# power.net
KiCad netlist of a schematic drawn in Altium Designer
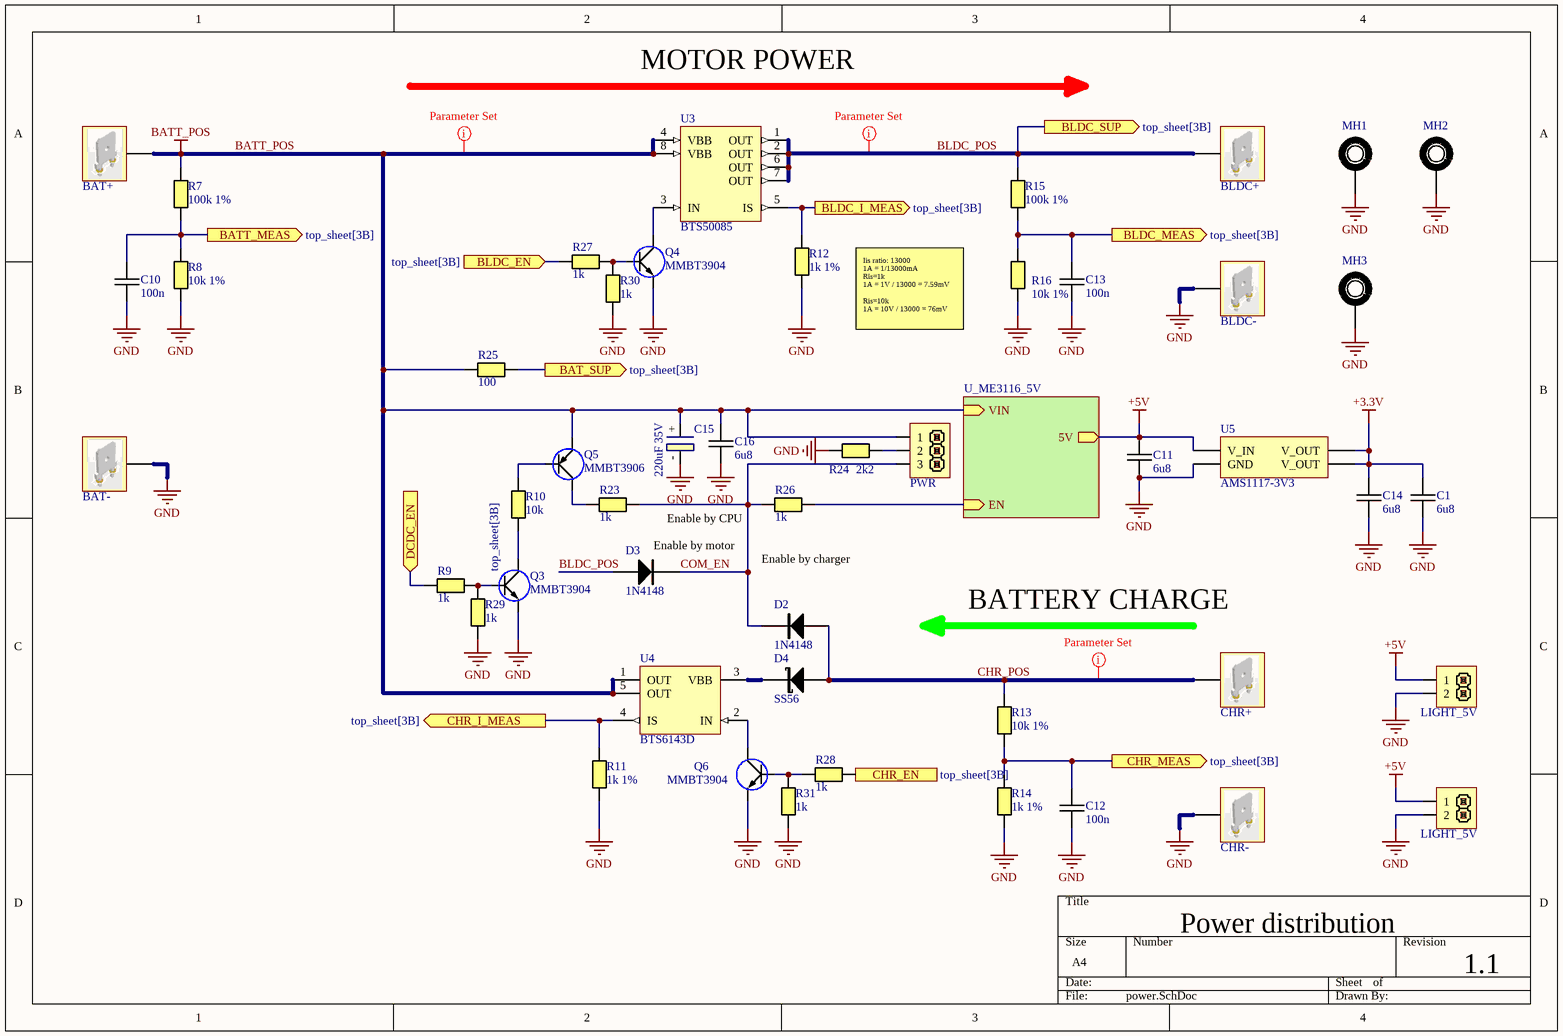
[diagram p0: power.SchDoc]

(export (version "E")
  (design (tool "Eeschema 10.0.6"))
  (components
    (comp (ref "BAT+")
      (value "Crimp 6.3 single PCB")
      (footprint "Crimp 6.3mm single PCB")
      (description "Straight Mount Angle PCB Tab Terminal")
      (libsource (lib "") (part "Crimp 6.3 single PCB_1"))
    )
    (comp (ref "BAT-")
      (value "Crimp 6.3 single PCB")
      (footprint "Crimp 6.3mm single PCB")
      (description "Straight Mount Angle PCB Tab Terminal")
      (libsource (lib "") (part "Crimp 6.3 single PCB_1"))
    )
    (comp (ref "BLDC+")
      (value "Crimp 6.3 single PCB")
      (footprint "Crimp 6.3mm single PCB")
      (description "Straight Mount Angle PCB Tab Terminal")
      (libsource (lib "Connectors") (part "Crimp 6.3 single PCB"))
    )
    (comp (ref "BLDC-")
      (value "Crimp 6.3 single PCB")
      (footprint "Crimp 6.3mm single PCB")
      (description "Straight Mount Angle PCB Tab Terminal")
      (libsource (lib "Connectors") (part "Crimp 6.3 single PCB"))
    )
    (comp (ref "C1")
      (value "6u8")
      (footprint "CAPC0805(2012)75_N")
      (description "Ceramic capacitor Medium density")
      (libsource (lib "Discrete") (part "Capacitor M"))
    )
    (comp (ref "C10")
      (value "100n")
      (footprint "CAPC0603(1608)55_N")
      (description "Ceramic capacitor Medium density")
      (libsource (lib "Discrete") (part "Capacitor M"))
    )
    (comp (ref "C11")
      (value "6u8")
      (footprint "CAPC0805(2012)75_N")
      (description "Ceramic capacitor Medium density")
      (libsource (lib "Discrete") (part "Capacitor M"))
    )
    (comp (ref "C12")
      (value "100n")
      (footprint "CAPC0603(1608)55_N")
      (description "Ceramic capacitor Medium density")
      (libsource (lib "Discrete") (part "Capacitor M"))
    )
    (comp (ref "C13")
      (value "100n")
      (footprint "CAPC0603(1608)55_N")
      (description "Ceramic capacitor Medium density")
      (libsource (lib "Discrete") (part "Capacitor M"))
    )
    (comp (ref "C14")
      (value "6u8")
      (footprint "CAPC0805(2012)75_N")
      (description "Ceramic capacitor Medium density")
      (libsource (lib "Discrete") (part "Capacitor M"))
    )
    (comp (ref "C15")
      (value "220uF 35V")
      (footprint "10x10.5 Capacitor")
      (description "Capacitor Electrolitic")
      (libsource (lib "Discrete") (part "Capacitor Electrolitic"))
    )
    (comp (ref "C16")
      (value "6u8")
      (footprint "CAPC0805(2012)75_N")
      (description "Ceramic capacitor Medium density")
      (libsource (lib "Discrete") (part "Capacitor M"))
    )
    (comp (ref "CHR+")
      (value "Crimp 6.3 single PCB")
      (footprint "Crimp 6.3mm single PCB")
      (description "Straight Mount Angle PCB Tab Terminal")
      (libsource (lib "Connectors") (part "Crimp 6.3 single PCB"))
    )
    (comp (ref "CHR-")
      (value "Crimp 6.3 single PCB")
      (footprint "Crimp 6.3mm single PCB")
      (description "Straight Mount Angle PCB Tab Terminal")
      (libsource (lib "Connectors") (part "Crimp 6.3 single PCB"))
    )
    (comp (ref "CN1")
      (value "PIN HEADER 1x2")
      (footprint "XH2.54 2P")
      (description "LIGHT_5V")
      (fields (field (name "PARAMETER 1") "LIGHT_5V"))
      (libsource (lib "Connectors") (part "PIN HEADER 2.54 1x2"))
    )
    (comp (ref "CN2")
      (value "PIN HEADER 1x2")
      (footprint "XH2.54 2P")
      (description "LIGHT_5V")
      (fields (field (name "PARAMETER 1") "LIGHT_5V"))
      (libsource (lib "Connectors") (part "PIN HEADER 2.54 1x2"))
    )
    (comp (ref "D2")
      (value "1N4148")
      (footprint "SOD80")
      (description "Small Signal Fast Switching Diodes")
      (libsource (lib "Diodes") (part "1N4148"))
    )
    (comp (ref "D3")
      (value "1N4148")
      (footprint "SOD80")
      (description "Small Signal Fast Switching Diodes")
      (libsource (lib "Diodes") (part "1N4148"))
    )
    (comp (ref "D4")
      (value "SS56")
      (footprint "SMAG")
      (description "Surface Mount Schottky Barrier Rectifier")
      (libsource (lib "Diodes") (part "SS56"))
    )
    (comp (ref "MH1")
      (value "Mounting Hole")
      (footprint "MH_M3")
      (libsource (lib "Connectors") (part "Mounting Hole"))
    )
    (comp (ref "MH2")
      (value "Mounting Hole")
      (footprint "MH_M3")
      (libsource (lib "Connectors") (part "Mounting Hole"))
    )
    (comp (ref "MH3")
      (value "Mounting Hole")
      (footprint "MH_M3")
      (libsource (lib "Connectors") (part "Mounting Hole"))
    )
    (comp (ref "PWR")
      (value "PIN HEADER 1x3")
      (footprint "XH2.54 3P")
      (libsource (lib "Connectors") (part "PIN HEADER 2.54 1x3"))
    )
    (comp (ref "Q3")
      (value "MMBT3904")
      (footprint "SOT23")
      (description "NPN General Purpose Transistor")
      (libsource (lib "Transistors") (part "2N3904"))
    )
    (comp (ref "Q4")
      (value "MMBT3904")
      (footprint "SOT23")
      (description "NPN General Purpose Transistor")
      (libsource (lib "Transistors") (part "2N3904"))
    )
    (comp (ref "Q5")
      (value "MMBT3906")
      (footprint "SOT23")
      (description "PNP General Purpose Transistor")
      (libsource (lib "Transistors") (part "2N3906"))
    )
    (comp (ref "Q6")
      (value "MMBT3904")
      (footprint "SOT23")
      (description "NPN General Purpose Transistor")
      (libsource (lib "Transistors") (part "2N3904"))
    )
    (comp (ref "R7")
      (value "100k 1%")
      (footprint "RESC0603(1608)_N")
      (description "Resistor Medium Density")
      (libsource (lib "") (part "Resistor M_1"))
    )
    (comp (ref "R8")
      (value "10k 1%")
      (footprint "RESC0603(1608)_N")
      (description "Resistor Medium Density")
      (libsource (lib "") (part "Resistor M_1"))
    )
    (comp (ref "R9")
      (value "1k")
      (footprint "RESC0603(1608)_N")
      (description "Resistor Medium Density")
      (libsource (lib "") (part "Resistor M_2"))
    )
    (comp (ref "R10")
      (value "10k")
      (footprint "RESC0603(1608)_N")
      (description "Resistor Medium Density")
      (libsource (lib "Discrete") (part "Resistor M"))
    )
    (comp (ref "R11")
      (value "1k 1%")
      (footprint "RESC0603(1608)_N")
      (description "Resistor Medium Density")
      (libsource (lib "") (part "Resistor M_1"))
    )
    (comp (ref "R12")
      (value "1k 1%")
      (footprint "RESC0603(1608)_N")
      (description "Resistor Medium Density")
      (libsource (lib "") (part "Resistor M_1"))
    )
    (comp (ref "R13")
      (value "10k 1%")
      (footprint "RESC0603(1608)_N")
      (description "Resistor Medium Density")
      (libsource (lib "") (part "Resistor M_1"))
    )
    (comp (ref "R14")
      (value "1k 1%")
      (footprint "RESC0603(1608)_N")
      (description "Resistor Medium Density")
      (libsource (lib "") (part "Resistor M_1"))
    )
    (comp (ref "R15")
      (value "100k 1%")
      (footprint "RESC0603(1608)_N")
      (description "Resistor Medium Density")
      (libsource (lib "") (part "Resistor M_1"))
    )
    (comp (ref "R16")
      (value "10k 1%")
      (footprint "RESC0603(1608)_N")
      (description "Resistor Medium Density")
      (libsource (lib "") (part "Resistor M_1"))
    )
    (comp (ref "R23")
      (value "1k")
      (footprint "RESC0603(1608)_N")
      (description "Resistor Medium Density")
      (libsource (lib "") (part "Resistor M_3"))
    )
    (comp (ref "R24")
      (value "2k2")
      (footprint "RESC0603(1608)_N")
      (description "Resistor Medium Density")
      (libsource (lib "") (part "Resistor M_3"))
    )
    (comp (ref "R25")
      (value "100")
      (footprint "RESC0603(1608)_N")
      (description "Resistor Medium Density")
      (libsource (lib "") (part "Resistor M_3"))
    )
    (comp (ref "R26")
      (value "1k")
      (footprint "RESC0603(1608)_N")
      (description "Resistor Medium Density")
      (libsource (lib "") (part "Resistor M_3"))
    )
    (comp (ref "R27")
      (value "1k")
      (footprint "RESC0603(1608)_N")
      (description "Resistor Medium Density")
      (libsource (lib "") (part "Resistor M_2"))
    )
    (comp (ref "R28")
      (value "1k")
      (footprint "RESC0603(1608)_N")
      (description "Resistor Medium Density")
      (libsource (lib "Discrete") (part "Resistor M"))
    )
    (comp (ref "R29")
      (value "1k")
      (footprint "RESC0603(1608)_N")
      (description "Resistor Medium Density")
      (libsource (lib "") (part "Resistor M_1"))
    )
    (comp (ref "R30")
      (value "1k")
      (footprint "RESC0603(1608)_N")
      (description "Resistor Medium Density")
      (libsource (lib "") (part "Resistor M_1"))
    )
    (comp (ref "R31")
      (value "1k")
      (footprint "RESC0603(1608)_N")
      (description "Resistor Medium Density")
      (libsource (lib "") (part "Resistor M_1"))
    )
    (comp (ref "U3")
      (value "BTS50085")
      (footprint "PG-TO220-7-4")
      (description "Smart Highside High Current Power Switch")
      (libsource (lib "Switches") (part "BTS50085-1TMA"))
    )
    (comp (ref "U4")
      (value "BTS6143D")
      (footprint "ITO252-5-11_M")
      (fields (field (name "MANUFACTURER") "Infineon"))
      (libsource (lib "Switches") (part "BTS6143D"))
    )
    (comp (ref "U5")
      (value "AMS1117-3V3")
      (footprint "SOT229P700X180-4N")
      (description "800mA LDO  15V max")
      (libsource (lib "VoltageRegulators") (part "AMS1117"))
    )
  )
  (nets
    (net (code "1") (name "+3.3V") (class "Default")
      (node (ref "C1") (pin "1") (pinfunction "1_1") (pintype "passive"))
      (node (ref "C14") (pin "1") (pinfunction "1_1") (pintype "passive"))
      (node (ref "U5") (pin "2") (pinfunction "V_OUT_2") (pintype "passive"))
      (node (ref "U5") (pin "4") (pinfunction "V_OUT_4") (pintype "passive"))
    )
    (net (code "2") (name "+5V") (class "Default")
      (node (ref "C11") (pin "1") (pinfunction "1_1") (pintype "passive"))
      (node (ref "CN1") (pin "1") (pinfunction "1_1") (pintype "passive"))
      (node (ref "CN2") (pin "1") (pinfunction "1_1") (pintype "passive"))
      (node (ref "U5") (pin "3") (pinfunction "V_IN_3") (pintype "passive"))
    )
    (net (code "3") (name "/BATT_MEAS") (class "Default")
      (node (ref "C10") (pin "1") (pinfunction "1_1") (pintype "passive"))
      (node (ref "R7") (pin "1") (pinfunction "1_1") (pintype "passive"))
      (node (ref "R8") (pin "2") (pinfunction "2_2") (pintype "passive"))
    )
    (net (code "4") (name "/BAT_SUP") (class "Default")
      (node (ref "R25") (pin "1") (pinfunction "1_1") (pintype "passive"))
    )
    (net (code "5") (name "/BLDC_EN") (class "Default")
      (node (ref "R27") (pin "1") (pinfunction "1_1") (pintype "passive"))
    )
    (net (code "6") (name "/BLDC_I_MEAS") (class "Default")
      (node (ref "R12") (pin "2") (pinfunction "2_2") (pintype "passive"))
      (node (ref "U3") (pin "5") (pinfunction "IS_5") (pintype "output"))
    )
    (net (code "7") (name "/BLDC_MEAS") (class "Default")
      (node (ref "C13") (pin "1") (pinfunction "1_1") (pintype "passive"))
      (node (ref "R15") (pin "1") (pinfunction "1_1") (pintype "passive"))
      (node (ref "R16") (pin "2") (pinfunction "2_2") (pintype "passive"))
    )
    (net (code "8") (name "/BLDC_POS") (class "Default")
      (node (ref "BLDC+") (pin "1") (pintype "passive"))
      (node (ref "D3") (pin "1") (pinfunction "A_1") (pintype "passive"))
      (node (ref "R15") (pin "2") (pinfunction "2_2") (pintype "passive"))
      (node (ref "U3") (pin "1") (pinfunction "OUT_1") (pintype "output"))
      (node (ref "U3") (pin "2") (pinfunction "OUT_2") (pintype "output"))
      (node (ref "U3") (pin "6") (pinfunction "OUT_6") (pintype "output"))
      (node (ref "U3") (pin "7") (pinfunction "OUT_7") (pintype "output"))
    )
    (net (code "9") (name "/CHR_EN") (class "Default")
      (node (ref "R28") (pin "1") (pinfunction "1_1") (pintype "passive"))
    )
    (net (code "10") (name "/CHR_I_MEAS") (class "Default")
      (node (ref "R11") (pin "2") (pinfunction "2_2") (pintype "passive"))
      (node (ref "U4") (pin "4") (pinfunction "IS_4") (pintype "output"))
    )
    (net (code "11") (name "/CHR_MEAS") (class "Default")
      (node (ref "C12") (pin "1") (pinfunction "1_1") (pintype "passive"))
      (node (ref "R13") (pin "1") (pinfunction "1_1") (pintype "passive"))
      (node (ref "R14") (pin "2") (pinfunction "2_2") (pintype "passive"))
    )
    (net (code "12") (name "/CHR_POS") (class "Default")
      (node (ref "CHR+") (pin "1") (pintype "passive"))
      (node (ref "D2") (pin "1") (pinfunction "A_1") (pintype "passive"))
      (node (ref "D4") (pin "2") (pinfunction "A_2") (pintype "passive"))
      (node (ref "R13") (pin "2") (pinfunction "2_2") (pintype "passive"))
    )
    (net (code "13") (name "/COM_EN") (class "Default")
      (node (ref "D2") (pin "2") (pinfunction "K_2") (pintype "passive"))
      (node (ref "D3") (pin "2") (pinfunction "K_2") (pintype "passive"))
      (node (ref "PWR") (pin "3") (pinfunction "3_3") (pintype "passive"))
      (node (ref "R23") (pin "1") (pinfunction "1_1") (pintype "passive"))
      (node (ref "R26") (pin "2") (pinfunction "2_2") (pintype "passive"))
    )
    (net (code "14") (name "/DCDC_EN") (class "Default")
      (node (ref "R9") (pin "1") (pinfunction "1_1") (pintype "passive"))
    )
    (net (code "15") (name "/EN") (class "Default")
      (node (ref "R26") (pin "1") (pinfunction "1_1") (pintype "passive"))
    )
    (net (code "16") (name "BATT_POS") (class "Default")
      (node (ref "BAT+") (pin "1") (pintype "passive"))
      (node (ref "C15") (pin "+") (pinfunction "+_+") (pintype "passive"))
      (node (ref "C16") (pin "2") (pinfunction "2_2") (pintype "passive"))
      (node (ref "PWR") (pin "1") (pinfunction "1_1") (pintype "passive"))
      (node (ref "Q5") (pin "2") (pinfunction "E_2") (pintype "passive"))
      (node (ref "R25") (pin "2") (pinfunction "2_2") (pintype "passive"))
      (node (ref "R7") (pin "2") (pinfunction "2_2") (pintype "passive"))
      (node (ref "U3") (pin "4") (pinfunction "VBB_4") (pintype "input"))
      (node (ref "U3") (pin "8") (pinfunction "VBB_8") (pintype "input"))
      (node (ref "U4") (pin "1") (pinfunction "OUT_1") (pintype "tri_state"))
      (node (ref "U4") (pin "5") (pinfunction "OUT_5") (pintype "tri_state"))
    )
    (net (code "17") (name "GND") (class "Default")
      (node (ref "BAT-") (pin "1") (pintype "passive"))
      (node (ref "BLDC-") (pin "1") (pintype "passive"))
      (node (ref "C1") (pin "2") (pinfunction "2_2") (pintype "passive"))
      (node (ref "C10") (pin "2") (pinfunction "2_2") (pintype "passive"))
      (node (ref "C11") (pin "2") (pinfunction "2_2") (pintype "passive"))
      (node (ref "C12") (pin "2") (pinfunction "2_2") (pintype "passive"))
      (node (ref "C13") (pin "2") (pinfunction "2_2") (pintype "passive"))
      (node (ref "C14") (pin "2") (pinfunction "2_2") (pintype "passive"))
      (node (ref "C15") (pin "-") (pinfunction "-_-") (pintype "passive"))
      (node (ref "C16") (pin "1") (pinfunction "1_1") (pintype "passive"))
      (node (ref "CHR-") (pin "1") (pintype "passive"))
      (node (ref "CN1") (pin "2") (pinfunction "2_2") (pintype "passive"))
      (node (ref "CN2") (pin "2") (pinfunction "2_2") (pintype "passive"))
      (node (ref "MH1") (pin "1") (pintype "passive"))
      (node (ref "MH2") (pin "1") (pintype "passive"))
      (node (ref "MH3") (pin "1") (pintype "passive"))
      (node (ref "Q3") (pin "2") (pinfunction "E_2") (pintype "passive"))
      (node (ref "Q4") (pin "2") (pinfunction "E_2") (pintype "passive"))
      (node (ref "Q6") (pin "2") (pinfunction "E_2") (pintype "passive"))
      (node (ref "R11") (pin "1") (pinfunction "1_1") (pintype "passive"))
      (node (ref "R12") (pin "1") (pinfunction "1_1") (pintype "passive"))
      (node (ref "R14") (pin "1") (pinfunction "1_1") (pintype "passive"))
      (node (ref "R16") (pin "1") (pinfunction "1_1") (pintype "passive"))
      (node (ref "R24") (pin "2") (pinfunction "2_2") (pintype "passive"))
      (node (ref "R29") (pin "1") (pinfunction "1_1") (pintype "passive"))
      (node (ref "R30") (pin "1") (pinfunction "1_1") (pintype "passive"))
      (node (ref "R31") (pin "1") (pinfunction "1_1") (pintype "passive"))
      (node (ref "R8") (pin "1") (pinfunction "1_1") (pintype "passive"))
      (node (ref "U5") (pin "1") (pinfunction "GND_1") (pintype "passive"))
    )
    (net (code "18") (name "Net-(D4-K)") (class "Default")
      (node (ref "D4") (pin "1") (pinfunction "K_1") (pintype "passive"))
      (node (ref "U4") (pin "3") (pinfunction "VBB_3") (pintype "power_in"))
    )
    (net (code "19") (name "Net-(PWR-Pad2)") (class "Default")
      (node (ref "PWR") (pin "2") (pinfunction "2_2") (pintype "passive"))
      (node (ref "R24") (pin "1") (pinfunction "1_1") (pintype "passive"))
    )
    (net (code "20") (name "Net-(Q3-B)") (class "Default")
      (node (ref "Q3") (pin "1") (pinfunction "B_1") (pintype "passive"))
      (node (ref "R29") (pin "2") (pinfunction "2_2") (pintype "passive"))
      (node (ref "R9") (pin "2") (pinfunction "2_2") (pintype "passive"))
    )
    (net (code "21") (name "Net-(Q3-C)") (class "Default")
      (node (ref "Q3") (pin "3") (pinfunction "C_3") (pintype "passive"))
      (node (ref "R10") (pin "2") (pinfunction "2_2") (pintype "passive"))
    )
    (net (code "22") (name "Net-(Q4-B)") (class "Default")
      (node (ref "Q4") (pin "1") (pinfunction "B_1") (pintype "passive"))
      (node (ref "R27") (pin "2") (pinfunction "2_2") (pintype "passive"))
      (node (ref "R30") (pin "2") (pinfunction "2_2") (pintype "passive"))
    )
    (net (code "23") (name "Net-(Q4-C)") (class "Default")
      (node (ref "Q4") (pin "3") (pinfunction "C_3") (pintype "passive"))
      (node (ref "U3") (pin "3") (pinfunction "IN_3") (pintype "input"))
    )
    (net (code "24") (name "Net-(Q5-B)") (class "Default")
      (node (ref "Q5") (pin "1") (pinfunction "B_1") (pintype "passive"))
      (node (ref "R10") (pin "1") (pinfunction "1_1") (pintype "passive"))
    )
    (net (code "25") (name "Net-(Q5-C)") (class "Default")
      (node (ref "Q5") (pin "3") (pinfunction "C_3") (pintype "passive"))
      (node (ref "R23") (pin "2") (pinfunction "2_2") (pintype "passive"))
    )
    (net (code "26") (name "Net-(Q6-B)") (class "Default")
      (node (ref "Q6") (pin "1") (pinfunction "B_1") (pintype "passive"))
      (node (ref "R28") (pin "2") (pinfunction "2_2") (pintype "passive"))
      (node (ref "R31") (pin "2") (pinfunction "2_2") (pintype "passive"))
    )
    (net (code "27") (name "Net-(Q6-C)") (class "Default")
      (node (ref "Q6") (pin "3") (pinfunction "C_3") (pintype "passive"))
      (node (ref "U4") (pin "2") (pinfunction "IN_2") (pintype "input"))
    )
  )
)
